# PWR_stage_AC.net
KiCad netlist of a schematic drawn in Altium Designer
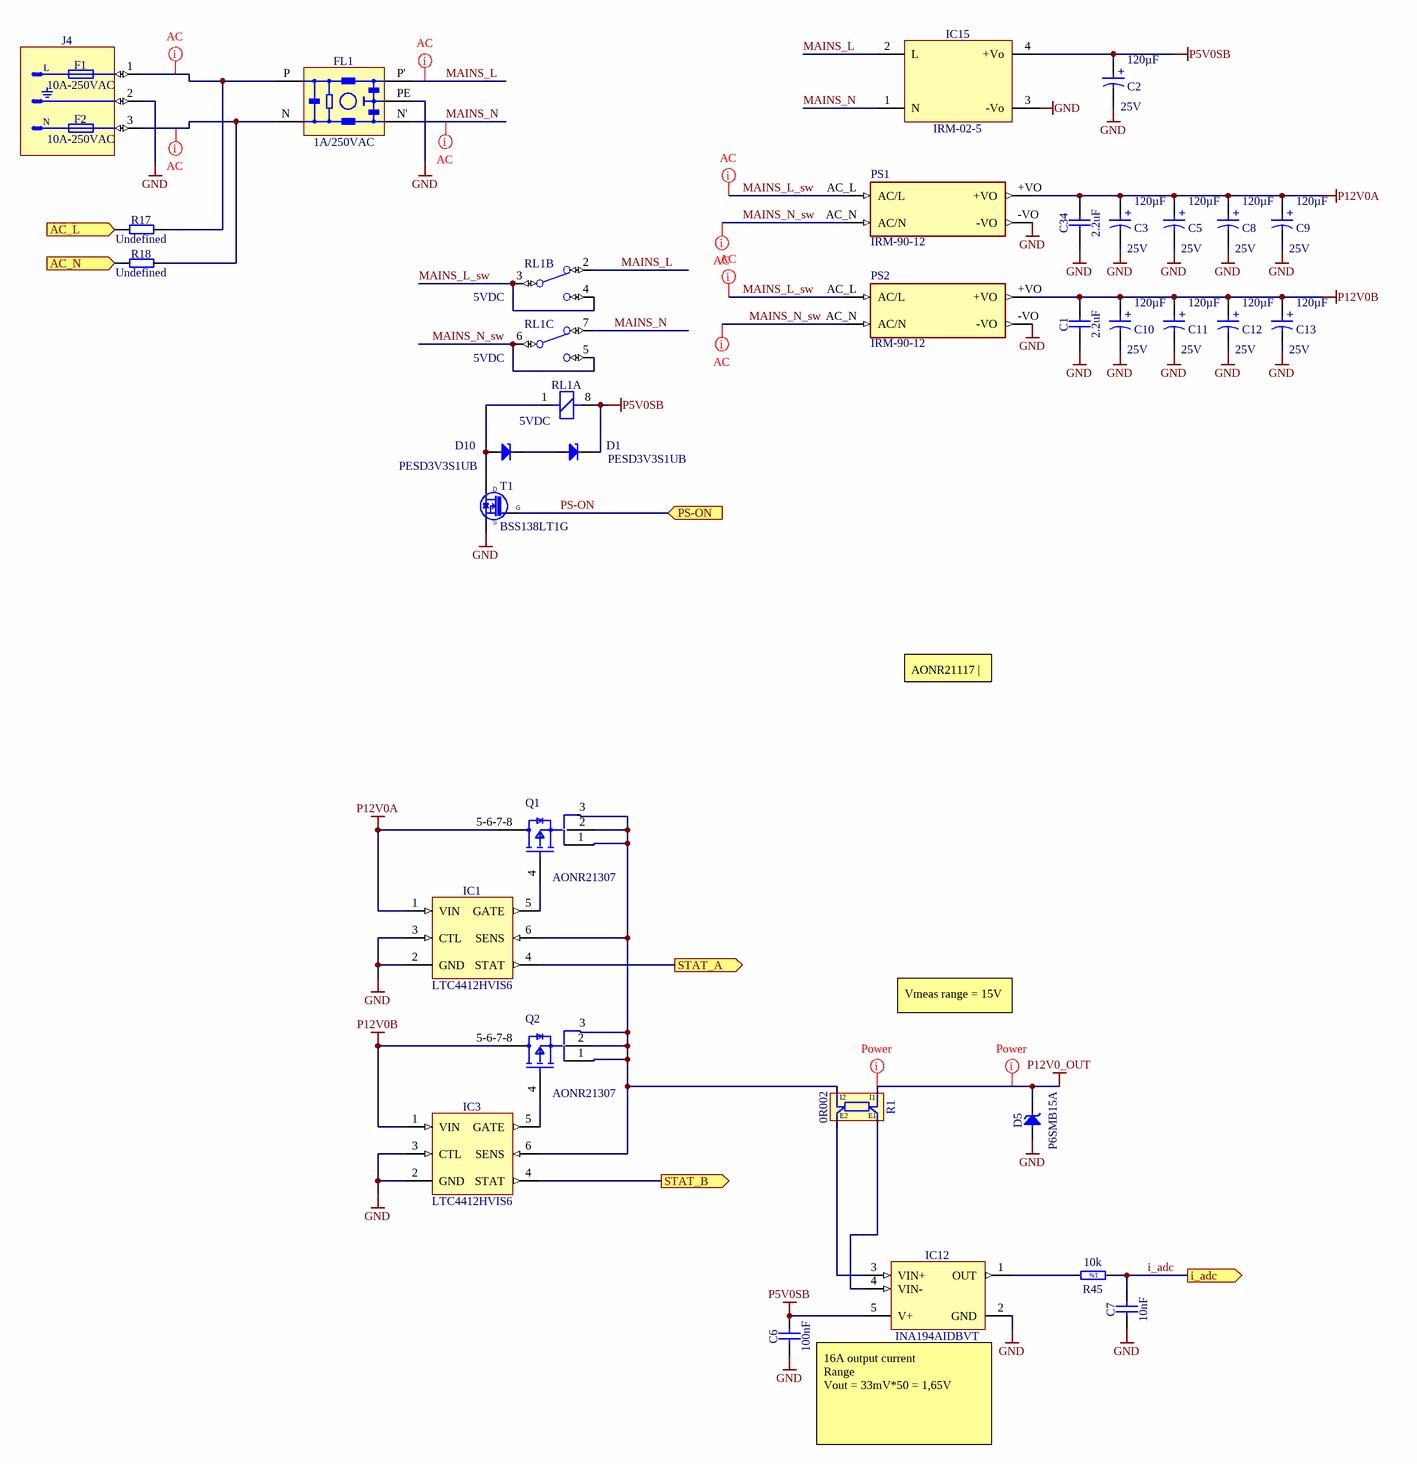
[diagram p0: PWR_stage_AC.SchDoc]

(export (version "E")
  (design (tool "Eeschema 10.0.6"))
  (components
    (comp (ref "C1")
      (value "2.2uF")
      (footprint "CAPC2013X145N")
      (description "Non-polarised capacitor")
      (fields
        (field (name "PART NUMBER") "CC0805_2.2UF_35V_10%_X7R_TDK_CGA4J1X7R1V225K125AC")
        (field (name "VOLTAGE") "35V")
        (field (name "AUTHOR") "CERN DEM BC")
      )
      (libsource (lib "Capacitors") (part "Capacitor - non polarized"))
    )
    (comp (ref "C2")
      (value "120µF")
      (footprint "WCAP-ATLI_D6.3H15")
      (description "WCAP-ATLI Aluminum Electrolytic Capacitor, Radial, THT, D6.3 x H15mm, 120µF, 25V")
      (fields
        (field (name "MANUFACTURER PART NUMBER") "860080473007")
        (field (name "MANUFACTURER") "Wurth Elektronik")
        (field (name "CAPACITANCE") "120µF")
        (field (name "RATED VOLTAGE (DC)") "25V")
      )
      (libsource (lib "Altium_WCAP-ATLI (rev22c)") (part "860080473007"))
    )
    (comp (ref "C3")
      (value "120µF")
      (footprint "WCAP-ATLI_D6.3H15")
      (description "WCAP-ATLI Aluminum Electrolytic Capacitor, Radial, THT, D6.3 x H15mm, 120µF, 25V")
      (fields
        (field (name "MANUFACTURER PART NUMBER") "860080473007")
        (field (name "MANUFACTURER") "Wurth Elektronik")
        (field (name "CAPACITANCE") "120µF")
        (field (name "RATED VOLTAGE (DC)") "25V")
      )
      (libsource (lib "Altium_WCAP-ATLI (rev22c)") (part "860080473007"))
    )
    (comp (ref "C5")
      (value "120µF")
      (footprint "WCAP-ATLI_D6.3H15")
      (description "WCAP-ATLI Aluminum Electrolytic Capacitor, Radial, THT, D6.3 x H15mm, 120µF, 25V")
      (fields
        (field (name "MANUFACTURER PART NUMBER") "860080473007")
        (field (name "MANUFACTURER") "Wurth Elektronik")
        (field (name "CAPACITANCE") "120µF")
        (field (name "RATED VOLTAGE (DC)") "25V")
      )
      (libsource (lib "Altium_WCAP-ATLI (rev22c)") (part "860080473007"))
    )
    (comp (ref "C6")
      (value "100nF")
      (footprint "CAPC1005X55N")
      (description "Non-polarised capacitor")
      (fields
        (field (name "PART NUMBER") "CC0402_100NF_25V_10%_X7R_YUDEN_TMK105B7104KVHF")
        (field (name "VOLTAGE") "25V")
        (field (name "AUTHOR") "CERN DEM JLC")
      )
      (libsource (lib "Capacitors") (part "Capacitor - non polarized"))
    )
    (comp (ref "C7")
      (value "10nF")
      (footprint "CAPC1005X55N")
      (description "Non-polarised capacitor")
      (fields
        (field (name "PART NUMBER") "CC0402_10NF_50V_10%_X7R")
        (field (name "VOLTAGE") "50V")
        (field (name "AUTHOR") "CERN DEM MR")
      )
      (libsource (lib "Capacitors") (part "Capacitor - non polarized"))
    )
    (comp (ref "C8")
      (value "120µF")
      (footprint "WCAP-ATLI_D6.3H15")
      (description "WCAP-ATLI Aluminum Electrolytic Capacitor, Radial, THT, D6.3 x H15mm, 120µF, 25V")
      (fields
        (field (name "MANUFACTURER PART NUMBER") "860080473007")
        (field (name "MANUFACTURER") "Wurth Elektronik")
        (field (name "CAPACITANCE") "120µF")
        (field (name "RATED VOLTAGE (DC)") "25V")
      )
      (libsource (lib "Altium_WCAP-ATLI (rev22c)") (part "860080473007"))
    )
    (comp (ref "C9")
      (value "120µF")
      (footprint "WCAP-ATLI_D6.3H15")
      (description "WCAP-ATLI Aluminum Electrolytic Capacitor, Radial, THT, D6.3 x H15mm, 120µF, 25V")
      (fields
        (field (name "MANUFACTURER PART NUMBER") "860080473007")
        (field (name "MANUFACTURER") "Wurth Elektronik")
        (field (name "CAPACITANCE") "120µF")
        (field (name "RATED VOLTAGE (DC)") "25V")
      )
      (libsource (lib "Altium_WCAP-ATLI (rev22c)") (part "860080473007"))
    )
    (comp (ref "C10")
      (value "120µF")
      (footprint "WCAP-ATLI_D6.3H15")
      (description "WCAP-ATLI Aluminum Electrolytic Capacitor, Radial, THT, D6.3 x H15mm, 120µF, 25V")
      (fields
        (field (name "MANUFACTURER PART NUMBER") "860080473007")
        (field (name "MANUFACTURER") "Wurth Elektronik")
        (field (name "CAPACITANCE") "120µF")
        (field (name "RATED VOLTAGE (DC)") "25V")
      )
      (libsource (lib "Altium_WCAP-ATLI (rev22c)") (part "860080473007"))
    )
    (comp (ref "C11")
      (value "120µF")
      (footprint "WCAP-ATLI_D6.3H15")
      (description "WCAP-ATLI Aluminum Electrolytic Capacitor, Radial, THT, D6.3 x H15mm, 120µF, 25V")
      (fields
        (field (name "MANUFACTURER PART NUMBER") "860080473007")
        (field (name "MANUFACTURER") "Wurth Elektronik")
        (field (name "CAPACITANCE") "120µF")
        (field (name "RATED VOLTAGE (DC)") "25V")
      )
      (libsource (lib "Altium_WCAP-ATLI (rev22c)") (part "860080473007"))
    )
    (comp (ref "C12")
      (value "120µF")
      (footprint "WCAP-ATLI_D6.3H15")
      (description "WCAP-ATLI Aluminum Electrolytic Capacitor, Radial, THT, D6.3 x H15mm, 120µF, 25V")
      (fields
        (field (name "MANUFACTURER PART NUMBER") "860080473007")
        (field (name "MANUFACTURER") "Wurth Elektronik")
        (field (name "CAPACITANCE") "120µF")
        (field (name "RATED VOLTAGE (DC)") "25V")
      )
      (libsource (lib "Altium_WCAP-ATLI (rev22c)") (part "860080473007"))
    )
    (comp (ref "C13")
      (value "120µF")
      (footprint "WCAP-ATLI_D6.3H15")
      (description "WCAP-ATLI Aluminum Electrolytic Capacitor, Radial, THT, D6.3 x H15mm, 120µF, 25V")
      (fields
        (field (name "MANUFACTURER PART NUMBER") "860080473007")
        (field (name "MANUFACTURER") "Wurth Elektronik")
        (field (name "CAPACITANCE") "120µF")
        (field (name "RATED VOLTAGE (DC)") "25V")
      )
      (libsource (lib "Altium_WCAP-ATLI (rev22c)") (part "860080473007"))
    )
    (comp (ref "C34")
      (value "2.2uF")
      (footprint "CAPC2013X145N")
      (description "Non-polarised capacitor")
      (fields
        (field (name "PART NUMBER") "CC0805_2.2UF_35V_10%_X7R_TDK_CGA4J1X7R1V225K125AC")
        (field (name "VOLTAGE") "35V")
        (field (name "AUTHOR") "CERN DEM BC")
      )
      (libsource (lib "Capacitors") (part "Capacitor - non polarized"))
    )
    (comp (ref "D1")
      (value "PESD3V3S1UB")
      (footprint "SODFL1608X65N")
      (description "ESD protection diode")
      (fields
        (field (name "VOLTAGE") "3V3")
        (field (name "POWER") "330W")
        (field (name "AUTHOR") "CERN DEM JLC")
      )
      (libsource (lib "ICs And Semiconductors") (part "Diode ESD"))
    )
    (comp (ref "D5")
      (value "P6SMB15A")
      (footprint "DIOM5436X261N")
      (description "Transient Voltage Suppressor Diode (Uni-Directional)")
      (fields
        (field (name "VOLTAGE") "15V")
        (field (name "POWER") "600W")
        (field (name "AUTHOR") "CERN DEM JLC")
      )
      (libsource (lib "ICs And Semiconductors") (part "Diode TVS Uni-Directional"))
    )
    (comp (ref "D10")
      (value "PESD3V3S1UB")
      (footprint "SODFL1608X65N")
      (description "ESD protection diode")
      (fields
        (field (name "VOLTAGE") "3V3")
        (field (name "POWER") "330W")
        (field (name "AUTHOR") "CERN DEM JLC")
      )
      (libsource (lib "ICs And Semiconductors") (part "Diode ESD"))
    )
    (comp (ref "F1")
      (value "10A-250VAC")
      (footprint "FUSE_5X20_GLASS_v")
      (description "Fuse")
      (fields
        (field (name "PART NUMBER") "FUSE_SCHURTER_0034.3127_v")
        (field (name "MANUFACTURER") "SCHURTER")
        (field (name "AUTHOR") "CERN DEM JLC")
      )
      (libsource (lib "Eletro-mechanical") (part "Fuse No Pin"))
    )
    (comp (ref "F2")
      (value "10A-250VAC")
      (footprint "FUSE_5X20_GLASS_v")
      (description "Fuse")
      (fields
        (field (name "PART NUMBER") "FUSE_SCHURTER_0034.3127_v")
        (field (name "MANUFACTURER") "SCHURTER")
        (field (name "AUTHOR") "CERN DEM JLC")
      )
      (libsource (lib "Eletro-mechanical") (part "Fuse No Pin"))
    )
    (comp (ref "FL1")
      (value "1A/250VAC")
      (footprint "FIL_SCHAFFNER_FN 406")
      (description "0.6 to 8.4A 230VAC Single Phase Ultra Compact EMC Filter")
      (fields
        (field (name "PART NUMBER") "FIL_SCHAFFNER_FN406-3-02")
        (field (name "MANUFACTURER") "SCHAFFNER")
        (field (name "AUTHOR") "CERN DEM JLC")
      )
      (libsource (lib "Inductors & Transformers") (part "FIL_SCHAFFNER_FN 406"))
    )
    (comp (ref "IC1")
      (value "LTC4412HVIS6")
      (footprint "SOT95P280X100-6N")
      (description "36V, Low Loss PowerPathTM Controller in ThinSOT")
      (fields
        (field (name "PART NUMBER") "LTC4412HVIS6#PBF")
        (field (name "MANUFACTURER") "LINEAR TECHNOLOGY")
        (field (name "AUTHOR") "CERN DEM JLC")
      )
      (libsource (lib "ICs And Semiconductors") (part "LTC4412HV"))
    )
    (comp (ref "IC3")
      (value "LTC4412HVIS6")
      (footprint "SOT95P280X100-6N")
      (description "36V, Low Loss PowerPathTM Controller in ThinSOT")
      (fields
        (field (name "PART NUMBER") "LTC4412HVIS6#PBF")
        (field (name "MANUFACTURER") "LINEAR TECHNOLOGY")
        (field (name "AUTHOR") "CERN DEM JLC")
      )
      (libsource (lib "ICs And Semiconductors") (part "LTC4412HV"))
    )
    (comp (ref "IC12")
      (value "INA194AIDBVT")
      (footprint "SOT95P280X145-5N")
      (description "Current Shunt Monitor -16V to +80V Common-Mode Range")
      (fields (field (name "MANUFACTURER") "TEXAS INSTRUMENTS") (field (name "AUTHOR") "CERN DEM JLC"))
      (libsource (lib "ICs And Semiconductors") (part "INA194"))
    )
    (comp (ref "IC15")
      (value "IRM-02-5")
      (footprint "PWS_MEANWELL_IRM-02")
      (description "Power Supply")
      (fields (field (name "MANUFACTURER") "MEAN WELL") (field (name "AUTHOR") "GK"))
      (libsource (lib "Regulators_SMPS") (part "AC_DC_IRM-02-5"))
    )
    (comp (ref "J4")
      (value "IEC")
      (footprint "SCHURTER_GSF1.2202.31")
      (description "Connector 3 Male 2P+ 2 Fuse Holder")
      (fields
        (field (name "PART NUMBER") "SCHURTER_GSF1.2201.31")
        (field (name "MANUFACTURER") "SCHURTER")
        (field (name "AUTHOR") "CERN DEM JMW")
      )
      (libsource (lib "Connectors") (part "Connector 3 Male 2P+T+2FUSH"))
    )
    (comp (ref "PS1")
      (value "IRM-90-12")
      (footprint "CONV_IRM-90-12")
      (fields (field (name "MF") "{'manufacturer': u'MEAN WELL USA Inc.'}"))
      (libsource (lib "Regulators_SMPS") (part "AC_DC_IRM-90-12"))
    )
    (comp (ref "PS2")
      (value "IRM-90-12")
      (footprint "CONV_IRM-90-12")
      (fields (field (name "MF") "{'manufacturer': u'MEAN WELL USA Inc.'}"))
      (libsource (lib "Regulators_SMPS") (part "AC_DC_IRM-90-12"))
    )
    (comp (ref "Q1")
      (value "AONR21307")
      (footprint "FP-DFN3x3A_8L_EP1_P-MFG")
      (description "MOSFET P-CH 30V 3X3 DFN")
      (fields
        (field (name "MANUFACTURER") "Alpha & Omega Semiconductor")
        (field (name "OCTOPART") "https://octopart.com/aonr21307-alpha+%26+omega+semiconductor-96014004")
      )
      (libsource (lib "") (part "930f9a8045f638e150331e36b7043a6_1"))
    )
    (comp (ref "Q2")
      (value "AONR21307")
      (footprint "FP-DFN3x3A_8L_EP1_P-MFG")
      (description "MOSFET P-CH 30V 3X3 DFN")
      (fields
        (field (name "MANUFACTURER") "Alpha & Omega Semiconductor")
        (field (name "OCTOPART") "https://octopart.com/aonr21307-alpha+%26+omega+semiconductor-96014004")
      )
      (libsource (lib "Altium Content Vault") (part "930f9a8045f638e150331e36b7043a6"))
    )
    (comp (ref "R1")
      (value "0R002")
      (footprint "RES_VISHAY_WSK2512_0R005-0R2")
      (description "Power and Current Sensing Resistor")
      (fields
        (field (name "PART NUMBER") "R2512_0R002_1%_1W_35PPM_VISHAY_WSK")
        (field (name "POWER") "1W")
        (field (name "AUTHOR") "CERN DEM MR")
      )
      (libsource (lib "Resistors") (part "Current Sense Resistor"))
    )
    (comp (ref "R17")
      (value "Undefined")
      (footprint "RESC6331X70N")
      (description "Resistor")
      (fields (field (name "PART NUMBER") "R2512_NO-VALUE") (field (name "AUTHOR") "CERN DEM JLC"))
      (libsource (lib "Resistors") (part "Resistor"))
    )
    (comp (ref "R18")
      (value "Undefined")
      (footprint "RESC6331X70N")
      (description "Resistor")
      (fields (field (name "PART NUMBER") "R2512_NO-VALUE") (field (name "AUTHOR") "CERN DEM JLC"))
      (libsource (lib "Resistors") (part "Resistor"))
    )
    (comp (ref "R45")
      (value "10k")
      (footprint "RESC1005X40N")
      (description "Resistor - 1%")
      (fields
        (field (name "PART NUMBER") "R0402_10K_1%_0.0625W_100PPM")
        (field (name "POWER") "0.0625W")
        (field (name "AUTHOR") "CERN DEM JLC")
      )
      (libsource (lib "Resistors") (part "Resistor - 1%"))
    )
    (comp (ref "RL1")
      (value "5VDC")
      (footprint "REL_OMRON_G2RL-2-5DC")
      (description "DPDT Power Relay, G2RL Series")
      (fields
        (field (name "PART NUMBER") "REL_OMRON_G2RL-2-5DC")
        (field (name "MANUFACTURER") "OMRON ELECTRONIC")
        (field (name "AUTHOR") "GK")
      )
      (libsource (lib "") (part "REL_OMRON_G2RL-24_1"))
    )
    (comp (ref "T1")
      (value "BSS138LT1G")
      (footprint "SOT95P240X110-3N")
      (description "N-CHANNEL MOSFET WITH DIODE")
      (fields (field (name "MANUFACTURER") "ON SEMICONDUCTOR") (field (name "AUTHOR") "CERN DEM JLC"))
      (libsource (lib "ICs And Semiconductors") (part "N-MOSFET-D 1G 2S 3D"))
    )
  )
  (nets
    (net (code "1") (name "/AC_L") (class "Default")
      (node (ref "R17") (pin "1") (pinfunction "1_1") (pintype "passive"))
    )
    (net (code "2") (name "/AC_N") (class "Default")
      (node (ref "R18") (pin "1") (pinfunction "1_1") (pintype "passive"))
    )
    (net (code "3") (name "/MAINS_L") (class "Default")
      (node (ref "FL1") (pin "P'") (pinfunction "P'_P'") (pintype "passive"))
      (node (ref "IC15") (pin "2") (pinfunction "L_2") (pintype "power_in"))
      (node (ref "RL1") (pin "2") (pinfunction "NC_2") (pintype "bidirectional"))
    )
    (net (code "4") (name "/MAINS_L_sw") (class "Default")
      (node (ref "PS1") (pin "AC_L") (pinfunction "AC/L_AC_L") (pintype "input"))
      (node (ref "PS2") (pin "AC_L") (pinfunction "AC/L_AC_L") (pintype "input"))
      (node (ref "RL1") (pin "3") (pinfunction "C_3") (pintype "bidirectional"))
      (node (ref "RL1") (pin "4") (pinfunction "NO_4") (pintype "bidirectional"))
    )
    (net (code "5") (name "/MAINS_N") (class "Default")
      (node (ref "FL1") (pin "N'") (pinfunction "N'_N'") (pintype "power_in"))
      (node (ref "IC15") (pin "1") (pinfunction "N_1") (pintype "power_in"))
      (node (ref "RL1") (pin "7") (pinfunction "NC_7") (pintype "bidirectional"))
    )
    (net (code "6") (name "/MAINS_N_sw") (class "Default")
      (node (ref "PS1") (pin "AC_N") (pinfunction "AC/N_AC_N") (pintype "input"))
      (node (ref "PS2") (pin "AC_N") (pinfunction "AC/N_AC_N") (pintype "input"))
      (node (ref "RL1") (pin "5") (pinfunction "NO_5") (pintype "bidirectional"))
      (node (ref "RL1") (pin "6") (pinfunction "C_6") (pintype "bidirectional"))
    )
    (net (code "7") (name "/PS-ON") (class "Default")
      (node (ref "T1") (pin "1") (pinfunction "G_1") (pintype "passive"))
    )
    (net (code "8") (name "/STAT_A") (class "Default")
      (node (ref "IC1") (pin "4") (pinfunction "STAT_4") (pintype "output"))
    )
    (net (code "9") (name "/STAT_B") (class "Default")
      (node (ref "IC3") (pin "4") (pinfunction "STAT_4") (pintype "output"))
    )
    (net (code "10") (name "/i_adc") (class "Default")
      (node (ref "C7") (pin "2") (pinfunction "2_2") (pintype "passive"))
      (node (ref "R45") (pin "1") (pinfunction "1_1") (pintype "passive"))
    )
    (net (code "11") (name "GND") (class "Default")
      (node (ref "C1") (pin "1") (pinfunction "1_1") (pintype "passive"))
      (node (ref "C10") (pin "2") (pinfunction "N_2") (pintype "passive"))
      (node (ref "C11") (pin "2") (pinfunction "N_2") (pintype "passive"))
      (node (ref "C12") (pin "2") (pinfunction "N_2") (pintype "passive"))
      (node (ref "C13") (pin "2") (pinfunction "N_2") (pintype "passive"))
      (node (ref "C2") (pin "2") (pinfunction "N_2") (pintype "passive"))
      (node (ref "C3") (pin "2") (pinfunction "N_2") (pintype "passive"))
      (node (ref "C34") (pin "1") (pinfunction "1_1") (pintype "passive"))
      (node (ref "C5") (pin "2") (pinfunction "N_2") (pintype "passive"))
      (node (ref "C6") (pin "1") (pinfunction "1_1") (pintype "passive"))
      (node (ref "C7") (pin "1") (pinfunction "1_1") (pintype "passive"))
      (node (ref "C8") (pin "2") (pinfunction "N_2") (pintype "passive"))
      (node (ref "C9") (pin "2") (pinfunction "N_2") (pintype "passive"))
      (node (ref "D5") (pin "2") (pinfunction "A_2") (pintype "passive"))
      (node (ref "FL1") (pin "PE") (pinfunction "PE_PE") (pintype "passive"))
      (node (ref "IC1") (pin "2") (pinfunction "GND_2") (pintype "power_in"))
      (node (ref "IC1") (pin "3") (pinfunction "CTL_3") (pintype "input"))
      (node (ref "IC12") (pin "2") (pinfunction "GND_2") (pintype "power_in"))
      (node (ref "IC15") (pin "3") (pinfunction "-Vo_3") (pintype "power_in"))
      (node (ref "IC3") (pin "2") (pinfunction "GND_2") (pintype "power_in"))
      (node (ref "IC3") (pin "3") (pinfunction "CTL_3") (pintype "input"))
      (node (ref "J4") (pin "2") (pinfunction "2_2") (pintype "bidirectional"))
      (node (ref "PS1") (pin "-VO") (pinfunction "-VO_-VO") (pintype "output"))
      (node (ref "PS2") (pin "-VO") (pinfunction "-VO_-VO") (pintype "output"))
      (node (ref "T1") (pin "2") (pinfunction "S_2") (pintype "passive"))
    )
    (net (code "12") (name "Net-(D1-A)") (class "Default")
      (node (ref "D1") (pin "2") (pinfunction "A_2") (pintype "passive"))
      (node (ref "D10") (pin "1") (pinfunction "C_1") (pintype "passive"))
    )
    (net (code "13") (name "Net-(D10-A)") (class "Default")
      (node (ref "D10") (pin "2") (pinfunction "A_2") (pintype "passive"))
      (node (ref "RL1") (pin "1") (pinfunction "1_1") (pintype "passive"))
      (node (ref "T1") (pin "3") (pinfunction "D_3") (pintype "passive"))
    )
    (net (code "14") (name "Net-(FL1-PadN)") (class "Default")
      (node (ref "FL1") (pin "N") (pinfunction "N_N") (pintype "passive"))
      (node (ref "J4") (pin "3") (pinfunction "3_3") (pintype "bidirectional"))
      (node (ref "R18") (pin "2") (pinfunction "2_2") (pintype "passive"))
    )
    (net (code "15") (name "Net-(FL1-PadP)") (class "Default")
      (node (ref "FL1") (pin "P") (pinfunction "P_P") (pintype "passive"))
      (node (ref "J4") (pin "1") (pinfunction "1_1") (pintype "bidirectional"))
      (node (ref "R17") (pin "2") (pinfunction "2_2") (pintype "passive"))
    )
    (net (code "16") (name "Net-(IC1-GATE)") (class "Default")
      (node (ref "IC1") (pin "5") (pinfunction "GATE_5") (pintype "output"))
      (node (ref "Q1") (pin "4") (pinfunction "G_4") (pintype "passive"))
    )
    (net (code "17") (name "Net-(IC1-SENS)") (class "Default")
      (node (ref "IC1") (pin "6") (pinfunction "SENS_6") (pintype "input"))
      (node (ref "IC3") (pin "6") (pinfunction "SENS_6") (pintype "input"))
      (node (ref "Q1") (pin "1") (pinfunction "S_1") (pintype "passive"))
      (node (ref "Q1") (pin "2") (pinfunction "S_2") (pintype "passive"))
      (node (ref "Q1") (pin "3") (pinfunction "S_3") (pintype "passive"))
      (node (ref "Q2") (pin "1") (pinfunction "S_1") (pintype "passive"))
      (node (ref "Q2") (pin "2") (pinfunction "S_2") (pintype "passive"))
      (node (ref "Q2") (pin "3") (pinfunction "S_3") (pintype "passive"))
      (node (ref "R1") (pin "I2") (pinfunction "I2_I2") (pintype "passive"))
    )
    (net (code "18") (name "Net-(IC3-GATE)") (class "Default")
      (node (ref "IC3") (pin "5") (pinfunction "GATE_5") (pintype "output"))
      (node (ref "Q2") (pin "4") (pinfunction "G_4") (pintype "passive"))
    )
    (net (code "19") (name "Net-(IC12-OUT)") (class "Default")
      (node (ref "IC12") (pin "1") (pinfunction "OUT_1") (pintype "output"))
      (node (ref "R45") (pin "2") (pinfunction "2_2") (pintype "passive"))
    )
    (net (code "20") (name "Net-(IC12-VIN+)") (class "Default")
      (node (ref "IC12") (pin "3") (pinfunction "VIN+_3") (pintype "input"))
      (node (ref "R1") (pin "E2") (pinfunction "E2_E2") (pintype "passive"))
    )
    (net (code "21") (name "Net-(IC12-VIN-)") (class "Default")
      (node (ref "IC12") (pin "4") (pinfunction "VIN-_4") (pintype "input"))
      (node (ref "R1") (pin "E1") (pinfunction "E1_E1") (pintype "passive"))
    )
    (net (code "22") (name "P5V0SB") (class "Default")
      (node (ref "C2") (pin "1") (pinfunction "P_1") (pintype "passive"))
      (node (ref "C6") (pin "2") (pinfunction "2_2") (pintype "passive"))
      (node (ref "D1") (pin "1") (pinfunction "C_1") (pintype "passive"))
      (node (ref "IC12") (pin "5") (pinfunction "V+_5") (pintype "power_in"))
      (node (ref "IC15") (pin "4") (pinfunction "+Vo_4") (pintype "power_in"))
      (node (ref "RL1") (pin "8") (pinfunction "8_8") (pintype "passive"))
    )
    (net (code "23") (name "P12V0A") (class "Default")
      (node (ref "C3") (pin "1") (pinfunction "P_1") (pintype "passive"))
      (node (ref "C34") (pin "2") (pinfunction "2_2") (pintype "passive"))
      (node (ref "C5") (pin "1") (pinfunction "P_1") (pintype "passive"))
      (node (ref "C8") (pin "1") (pinfunction "P_1") (pintype "passive"))
      (node (ref "C9") (pin "1") (pinfunction "P_1") (pintype "passive"))
      (node (ref "IC1") (pin "1") (pinfunction "VIN_1") (pintype "input"))
      (node (ref "PS1") (pin "+VO") (pinfunction "+VO_+VO") (pintype "output"))
      (node (ref "Q1") (pin "5-6-7-8") (pinfunction "D_5-6-7-8") (pintype "passive"))
    )
    (net (code "24") (name "P12V0B") (class "Default")
      (node (ref "C1") (pin "2") (pinfunction "2_2") (pintype "passive"))
      (node (ref "C10") (pin "1") (pinfunction "P_1") (pintype "passive"))
      (node (ref "C11") (pin "1") (pinfunction "P_1") (pintype "passive"))
      (node (ref "C12") (pin "1") (pinfunction "P_1") (pintype "passive"))
      (node (ref "C13") (pin "1") (pinfunction "P_1") (pintype "passive"))
      (node (ref "IC3") (pin "1") (pinfunction "VIN_1") (pintype "input"))
      (node (ref "PS2") (pin "+VO") (pinfunction "+VO_+VO") (pintype "output"))
      (node (ref "Q2") (pin "5-6-7-8") (pinfunction "D_5-6-7-8") (pintype "passive"))
    )
    (net (code "25") (name "P12V0_OUT") (class "Default")
      (node (ref "D5") (pin "1") (pinfunction "C_1") (pintype "passive"))
      (node (ref "R1") (pin "I1") (pinfunction "I1_I1") (pintype "passive"))
    )
  )
)
